# booster_sheet.net
KiCad netlist of a schematic drawn in Altium Designer
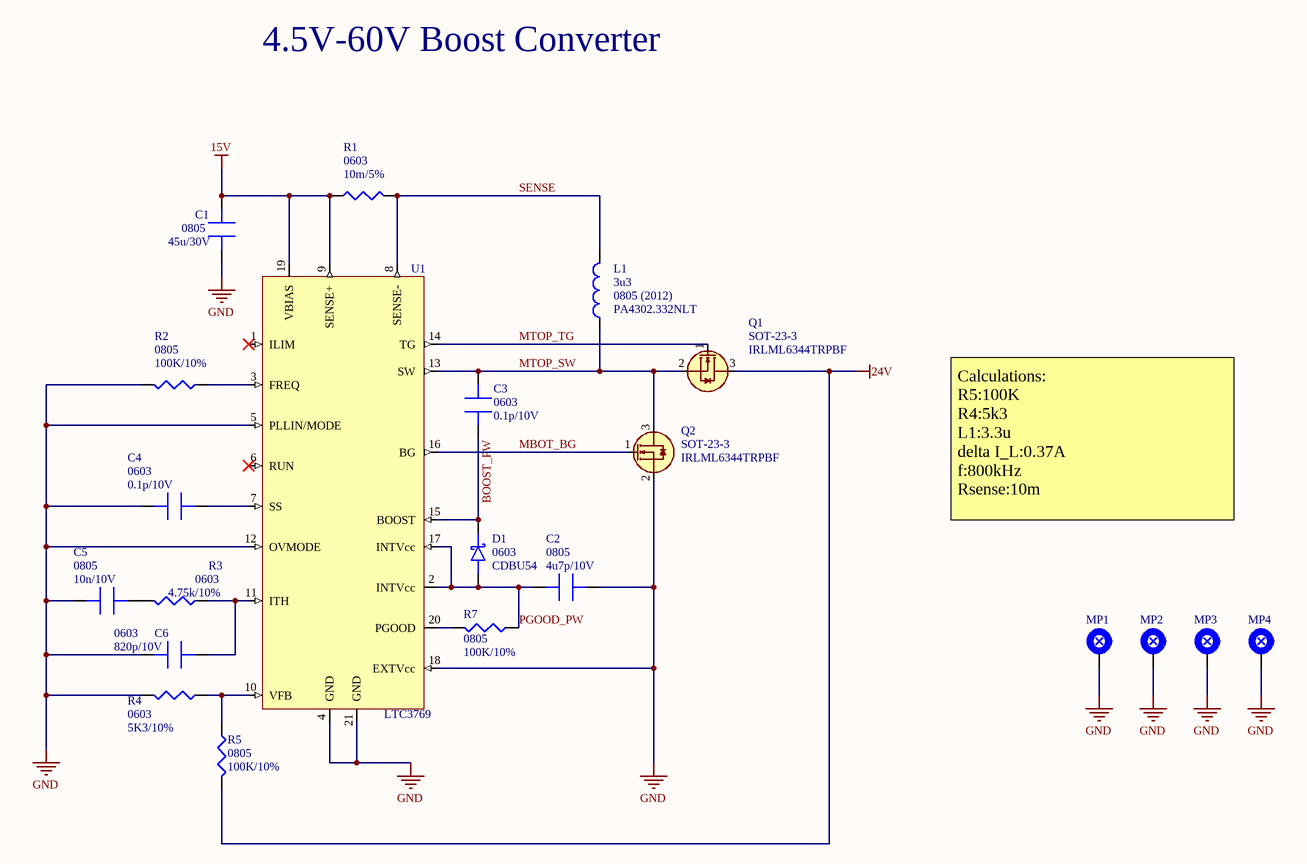
[diagram p0: booster_sheet.SchDoc]

(export (version "E")
  (design (tool "Eeschema 10.0.6"))
  (components
    (comp (ref "C1")
      (value "45u/30V")
      (footprint "CAPC2012X09L [0805]")
      (description "Standard capacitor")
      (fields (field (name "PACKAGE") "0805") (field (name "Comment") "C"))
      (libsource (lib "SR_Library") (part "C"))
    )
    (comp (ref "C2")
      (value "4u7p/10V")
      (footprint "CAPC2012X09L [0805]")
      (description "Standard capacitor")
      (fields (field (name "PACKAGE") "0805") (field (name "Comment") "C"))
      (libsource (lib "SR_Library") (part "C"))
    )
    (comp (ref "C3")
      (value "0.1p/10V")
      (footprint "CAPC1608X10L [0603]")
      (description "Standard capacitor")
      (fields (field (name "PACKAGE") "0603") (field (name "Comment") "C"))
      (libsource (lib "SR_Library") (part "C"))
    )
    (comp (ref "C4")
      (value "0.1p/10V")
      (footprint "CAPC1608X10L [0603]")
      (description "Standard capacitor")
      (fields (field (name "PACKAGE") "0603") (field (name "Comment") "C"))
      (libsource (lib "SR_Library") (part "C"))
    )
    (comp (ref "C5")
      (value "10n/10V")
      (footprint "CAPC2012X09L [0805]")
      (description "Standard capacitor")
      (fields (field (name "PACKAGE") "0805") (field (name "Comment") "C"))
      (libsource (lib "SR_Library") (part "C"))
    )
    (comp (ref "C6")
      (value "820p/10V")
      (footprint "CAPC1608X10L [0603]")
      (description "Standard capacitor")
      (fields (field (name "PACKAGE") "0603") (field (name "Comment") "C"))
      (libsource (lib "SR_Library") (part "C"))
    )
    (comp (ref "D1")
      (value "CDBU54")
      (footprint "DIOC1709X10N")
      (description "Schottky Diodes & Rectifiers VR=30V, IO=200mA")
      (fields (field (name "PACKAGE") "0603") (field (name "PN") "CDBU54"))
      (libsource (lib "SR_Library") (part "sSchottky"))
    )
    (comp (ref "L1")
      (value "3u3")
      (footprint "INDP7474X56N")
      (description "Fixed Inductors 3.3uH SMT Inductor 7.5 x 7.5 x 5.6mm")
      (fields
        (field (name "PACKAGE") "0805 (2012)")
        (field (name "PN") "PA4302.332NLT")
        (field (name "Comment") "PA4302.332NLT")
      )
      (libsource (lib "SR_Library") (part "Inductor"))
    )
    (comp (ref "MP1")
      (value "Mounting hole")
      (footprint "Mounting_hole_M3")
      (libsource (lib "SR_Library") (part "Mounting hole"))
    )
    (comp (ref "MP2")
      (value "Mounting hole")
      (footprint "Mounting_hole_M3")
      (libsource (lib "SR_Library") (part "Mounting hole"))
    )
    (comp (ref "MP3")
      (value "Mounting hole")
      (footprint "Mounting_hole_M3")
      (libsource (lib "SR_Library") (part "Mounting hole"))
    )
    (comp (ref "MP4")
      (value "Mounting hole")
      (footprint "Mounting_hole_M3")
      (libsource (lib "SR_Library") (part "Mounting hole"))
    )
    (comp (ref "Q1")
      (value "IRLML6344TRPBF")
      (footprint "SOT95P237X120-3N")
      (description "MOSFET MOSFT 5.0A 29mOhm 30V 2.5V drv capable")
      (fields (field (name "PACKAGE") "SOT-23-3") (field (name "PN") "IRLML6344TRPBF"))
      (libsource (lib "SR_Library") (part "sN-MOSFET"))
    )
    (comp (ref "Q2")
      (value "IRLML6344TRPBF")
      (footprint "SOT95P237X120-3N")
      (description "MOSFET MOSFT 5.0A 29mOhm 30V 2.5V drv capable")
      (fields (field (name "PACKAGE") "SOT-23-3") (field (name "PN") "IRLML6344TRPBF"))
      (libsource (lib "SR_Library") (part "sN-MOSFET"))
    )
    (comp (ref "R1")
      (value "10m/5%")
      (footprint "RESC1608X05L [0603]")
      (description "Standard resistor")
      (fields (field (name "PACKAGE") "0603") (field (name "Comment") "R"))
      (libsource (lib "SR_Library") (part "R"))
    )
    (comp (ref "R2")
      (value "100K/10%")
      (footprint "RESC2012X05L [0805]")
      (description "Standard resistor")
      (fields (field (name "PACKAGE") "0805") (field (name "Comment") "R"))
      (libsource (lib "SR_Library") (part "R"))
    )
    (comp (ref "R3")
      (value "4.75k/10%")
      (footprint "RESC1608X05L [0603]")
      (description "Standard resistor")
      (fields (field (name "PACKAGE") "0603") (field (name "Comment") "R"))
      (libsource (lib "SR_Library") (part "R"))
    )
    (comp (ref "R4")
      (value "5K3/10%")
      (footprint "RESC1608X05L [0603]")
      (description "Standard resistor")
      (fields (field (name "PACKAGE") "0603") (field (name "Comment") "R"))
      (libsource (lib "SR_Library") (part "R"))
    )
    (comp (ref "R5")
      (value "100K/10%")
      (footprint "RESC2012X05L [0805]")
      (description "Standard resistor")
      (fields (field (name "PACKAGE") "0805") (field (name "Comment") "R"))
      (libsource (lib "SR_Library") (part "R"))
    )
    (comp (ref "R7")
      (value "100K/10%")
      (footprint "RESC2012X05L [0805]")
      (description "Standard resistor")
      (fields (field (name "PACKAGE") "0805") (field (name "Comment") "R"))
      (libsource (lib "SR_Library") (part "R"))
    )
    (comp (ref "U1")
      (value "LTC3769")
      (footprint "LT3769FE")
      (description "Switching Voltage Regulators 60V Low IQ Synchronous Boost Controller")
      (libsource (lib "booster_sch_lib") (part "Booster"))
    )
  )
  (nets
    (net (code "1") (name "/BOOST_PW") (class "Default")
      (node (ref "C3") (pin "1") (pinfunction "1_1") (pintype "passive"))
      (node (ref "D1") (pin "1") (pinfunction "1_1") (pintype "passive"))
      (node (ref "U1") (pin "15") (pinfunction "BOOST_15") (pintype "input"))
    )
    (net (code "2") (name "/MBOT_BG") (class "Default")
      (node (ref "Q2") (pin "1") (pinfunction "1_1") (pintype "passive"))
      (node (ref "U1") (pin "16") (pinfunction "BG_16") (pintype "output"))
    )
    (net (code "3") (name "/MTOP_SW") (class "Default")
      (node (ref "C3") (pin "2") (pinfunction "2_2") (pintype "passive"))
      (node (ref "L1") (pin "1") (pinfunction "1_1") (pintype "passive"))
      (node (ref "Q1") (pin "2") (pinfunction "2_2") (pintype "passive"))
      (node (ref "Q2") (pin "3") (pinfunction "3_3") (pintype "passive"))
      (node (ref "U1") (pin "13") (pinfunction "SW_13") (pintype "output"))
    )
    (net (code "4") (name "/MTOP_TG") (class "Default")
      (node (ref "Q1") (pin "1") (pinfunction "1_1") (pintype "passive"))
      (node (ref "U1") (pin "14") (pinfunction "TG_14") (pintype "output"))
    )
    (net (code "5") (name "/PGOOD_PW") (class "Default")
      (node (ref "C2") (pin "2") (pinfunction "2_2") (pintype "passive"))
      (node (ref "D1") (pin "2") (pinfunction "2_2") (pintype "passive"))
      (node (ref "R7") (pin "2") (pinfunction "2_2") (pintype "passive"))
      (node (ref "U1") (pin "17") (pinfunction "INTVcc_17") (pintype "input"))
      (node (ref "U1") (pin "2") (pinfunction "INTVcc_2") (pintype "power_in"))
    )
    (net (code "6") (name "/SENSE") (class "Default")
      (node (ref "L1") (pin "2") (pinfunction "2_2") (pintype "passive"))
      (node (ref "R1") (pin "1") (pinfunction "1_1") (pintype "passive"))
      (node (ref "U1") (pin "8") (pinfunction "SENSE-_8") (pintype "output"))
    )
    (net (code "7") (name "15V") (class "Default")
      (node (ref "C1") (pin "2") (pinfunction "2_2") (pintype "passive"))
      (node (ref "R1") (pin "2") (pinfunction "2_2") (pintype "passive"))
      (node (ref "U1") (pin "19") (pinfunction "VBIAS_19") (pintype "power_in"))
      (node (ref "U1") (pin "9") (pinfunction "SENSE+_9") (pintype "output"))
    )
    (net (code "8") (name "24V") (class "Default")
      (node (ref "Q1") (pin "3") (pinfunction "3_3") (pintype "passive"))
      (node (ref "R5") (pin "1") (pinfunction "1_1") (pintype "passive"))
    )
    (net (code "9") (name "GND") (class "Default")
      (node (ref "C1") (pin "1") (pinfunction "1_1") (pintype "passive"))
      (node (ref "C2") (pin "1") (pinfunction "1_1") (pintype "passive"))
      (node (ref "C4") (pin "1") (pinfunction "1_1") (pintype "passive"))
      (node (ref "C5") (pin "1") (pinfunction "1_1") (pintype "passive"))
      (node (ref "C6") (pin "1") (pinfunction "1_1") (pintype "passive"))
      (node (ref "MP1") (pin "1") (pinfunction "1_1") (pintype "passive"))
      (node (ref "MP2") (pin "1") (pinfunction "1_1") (pintype "passive"))
      (node (ref "MP3") (pin "1") (pinfunction "1_1") (pintype "passive"))
      (node (ref "MP4") (pin "1") (pinfunction "1_1") (pintype "passive"))
      (node (ref "Q2") (pin "2") (pinfunction "2_2") (pintype "passive"))
      (node (ref "R2") (pin "1") (pinfunction "1_1") (pintype "passive"))
      (node (ref "R4") (pin "1") (pinfunction "1_1") (pintype "passive"))
      (node (ref "U1") (pin "12") (pinfunction "OVMODE_12") (pintype "input"))
      (node (ref "U1") (pin "18") (pinfunction "EXTVcc_18") (pintype "input"))
      (node (ref "U1") (pin "21") (pinfunction "GND_21") (pintype "power_in"))
      (node (ref "U1") (pin "4") (pinfunction "GND_4") (pintype "power_in"))
      (node (ref "U1") (pin "5") (pinfunction "PLLIN/MODE_5") (pintype "input"))
    )
    (net (code "10") (name "Net-(C5-Pad2)") (class "Default")
      (node (ref "C5") (pin "2") (pinfunction "2_2") (pintype "passive"))
      (node (ref "R3") (pin "1") (pinfunction "1_1") (pintype "passive"))
    )
    (net (code "11") (name "Net-(U1-FREQ)") (class "Default")
      (node (ref "R2") (pin "2") (pinfunction "2_2") (pintype "passive"))
      (node (ref "U1") (pin "3") (pinfunction "FREQ_3") (pintype "input"))
    )
    (net (code "12") (name "Net-(U1-ITH)") (class "Default")
      (node (ref "C6") (pin "2") (pinfunction "2_2") (pintype "passive"))
      (node (ref "R3") (pin "2") (pinfunction "2_2") (pintype "passive"))
      (node (ref "U1") (pin "11") (pinfunction "ITH_11") (pintype "input"))
    )
    (net (code "13") (name "Net-(U1-PGOOD)") (class "Default")
      (node (ref "R7") (pin "1") (pinfunction "1_1") (pintype "passive"))
      (node (ref "U1") (pin "20") (pinfunction "PGOOD_20") (pintype "power_in"))
    )
    (net (code "14") (name "Net-(U1-SS)") (class "Default")
      (node (ref "C4") (pin "2") (pinfunction "2_2") (pintype "passive"))
      (node (ref "U1") (pin "7") (pinfunction "SS_7") (pintype "input"))
    )
    (net (code "15") (name "Net-(U1-VFB)") (class "Default")
      (node (ref "R4") (pin "2") (pinfunction "2_2") (pintype "passive"))
      (node (ref "R5") (pin "2") (pinfunction "2_2") (pintype "passive"))
      (node (ref "U1") (pin "10") (pinfunction "VFB_10") (pintype "input"))
    )
    (net (code "16") (name "unconnected-(U1-ILIM-Pad1)") (class "Default")
      (node (ref "U1") (pin "1") (pinfunction "ILIM_1") (pintype "input+no_connect"))
    )
    (net (code "17") (name "unconnected-(U1-RUN-Pad6)") (class "Default")
      (node (ref "U1") (pin "6") (pinfunction "RUN_6") (pintype "input+no_connect"))
    )
  )
)
